# Pinout.net
KiCad netlist of a schematic drawn in Altium Designer
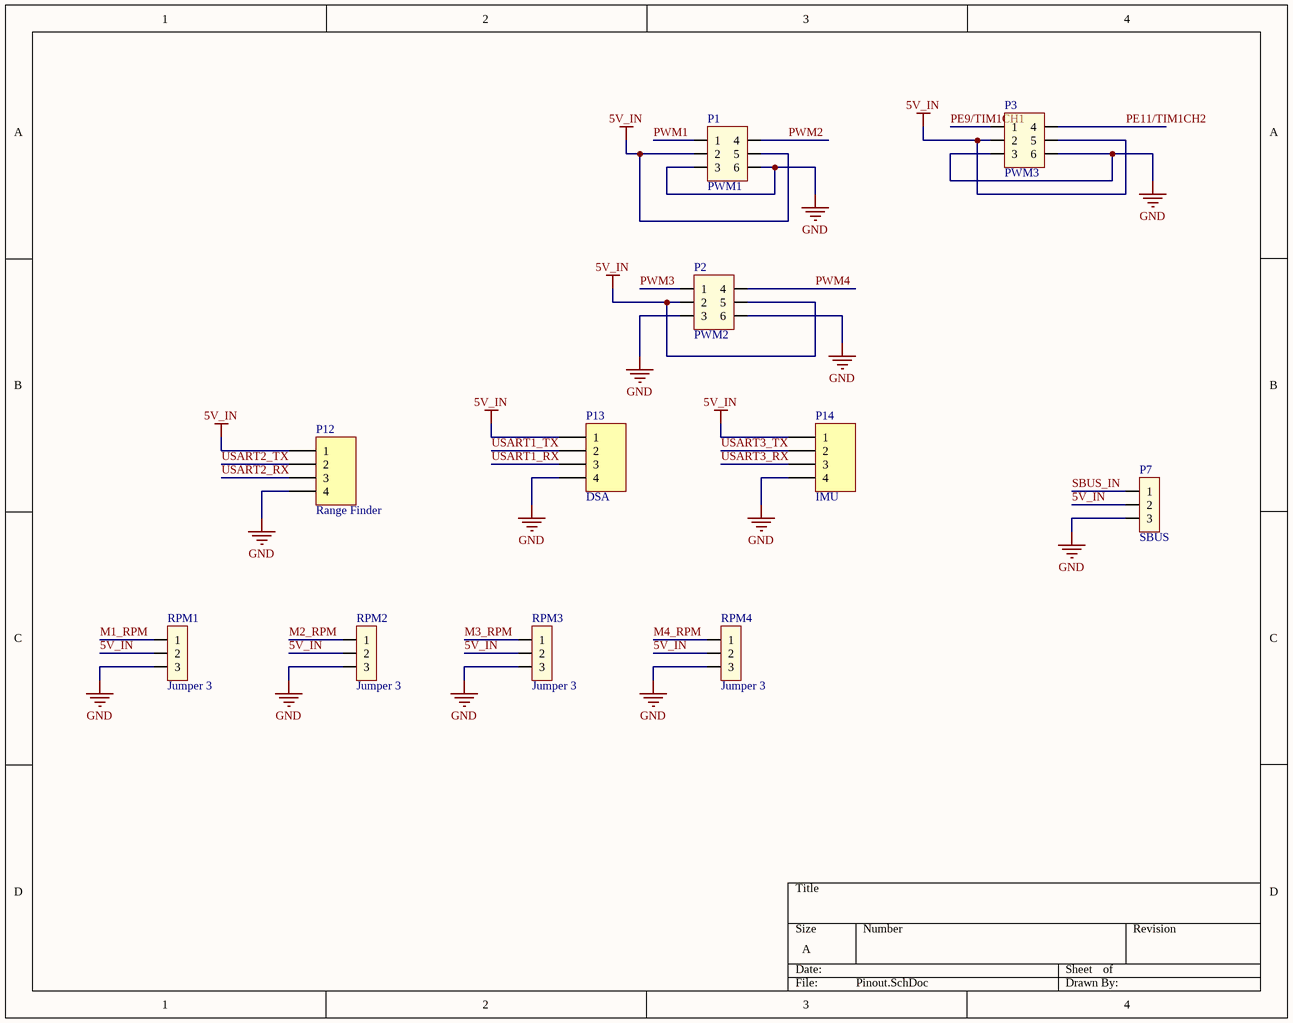
[diagram p0: Pinout.SchDoc]

(export (version "E")
  (design (tool "Eeschema 10.0.6"))
  (components
    (comp (ref "P1")
      (value "PWM1")
      (footprint "JP3x2")
      (description "Connector 3x2")
      (libsource (lib "syhaunguyen") (part "JP3x2"))
    )
    (comp (ref "P2")
      (value "PWM2")
      (footprint "JP3x2")
      (description "Connector 3x2")
      (libsource (lib "syhaunguyen") (part "JP3x2"))
    )
    (comp (ref "P3")
      (value "PWM3")
      (footprint "JP3x2")
      (description "Connector 3x2")
      (libsource (lib "syhaunguyen") (part "JP3x2"))
    )
    (comp (ref "P7")
      (value "SBUS")
      (footprint "JP3")
      (description "Jumper 3")
      (libsource (lib "syhaunguyen") (part "JP3"))
    )
    (comp (ref "P12")
      (value "Range Finder")
      (footprint "HDR1X4")
      (description "Header, 4-Pin")
      (fields (field (name "PUBLISHER") "Altium Limited"))
      (libsource (lib "Miscellaneous Connectors") (part "Header 4"))
    )
    (comp (ref "P13")
      (value "DSA")
      (footprint "HDR1X4")
      (description "Header, 4-Pin")
      (fields (field (name "PUBLISHER") "Altium Limited"))
      (libsource (lib "Miscellaneous Connectors") (part "Header 4"))
    )
    (comp (ref "P14")
      (value "IMU")
      (footprint "HDR1X4")
      (description "Header, 4-Pin")
      (fields (field (name "PUBLISHER") "Altium Limited"))
      (libsource (lib "Miscellaneous Connectors") (part "Header 4"))
    )
    (comp (ref "RPM1") (value "Jumper 3") (footprint "JP3") (libsource (lib "syhaunguyen") (part "JP3")))
    (comp (ref "RPM2") (value "Jumper 3") (footprint "JP3") (libsource (lib "syhaunguyen") (part "JP3")))
    (comp (ref "RPM3") (value "Jumper 3") (footprint "JP3") (libsource (lib "syhaunguyen") (part "JP3")))
    (comp (ref "RPM4") (value "Jumper 3") (footprint "JP3") (libsource (lib "syhaunguyen") (part "JP3")))
  )
  (nets
    (net (code "1") (name "/M1_RPM") (class "Default")
      (node (ref "RPM1") (pin "1") (pinfunction "1_1") (pintype "passive"))
    )
    (net (code "2") (name "/M2_RPM") (class "Default")
      (node (ref "RPM2") (pin "1") (pinfunction "1_1") (pintype "passive"))
    )
    (net (code "3") (name "/M3_RPM") (class "Default")
      (node (ref "RPM3") (pin "1") (pinfunction "1_1") (pintype "passive"))
    )
    (net (code "4") (name "/M4_RPM") (class "Default")
      (node (ref "RPM4") (pin "1") (pinfunction "1_1") (pintype "passive"))
    )
    (net (code "5") (name "/PE9{slash}TIM1CH1") (class "Default")
      (node (ref "P3") (pin "1") (pinfunction "1_1") (pintype "passive"))
    )
    (net (code "6") (name "/PE11{slash}TIM1CH2") (class "Default")
      (node (ref "P3") (pin "4") (pinfunction "4_4") (pintype "passive"))
    )
    (net (code "7") (name "/PWM1") (class "Default")
      (node (ref "P1") (pin "1") (pinfunction "1_1") (pintype "passive"))
    )
    (net (code "8") (name "/PWM2") (class "Default")
      (node (ref "P1") (pin "4") (pinfunction "4_4") (pintype "passive"))
    )
    (net (code "9") (name "/PWM3") (class "Default")
      (node (ref "P2") (pin "1") (pinfunction "1_1") (pintype "passive"))
    )
    (net (code "10") (name "/PWM4") (class "Default")
      (node (ref "P2") (pin "4") (pinfunction "4_4") (pintype "passive"))
    )
    (net (code "11") (name "/SBUS_IN") (class "Default")
      (node (ref "P7") (pin "1") (pinfunction "1_1") (pintype "passive"))
    )
    (net (code "12") (name "/USART1_RX") (class "Default")
      (node (ref "P13") (pin "3") (pinfunction "3_3") (pintype "passive"))
    )
    (net (code "13") (name "/USART1_TX") (class "Default")
      (node (ref "P13") (pin "2") (pinfunction "2_2") (pintype "passive"))
    )
    (net (code "14") (name "/USART2_RX") (class "Default")
      (node (ref "P12") (pin "3") (pinfunction "3_3") (pintype "passive"))
    )
    (net (code "15") (name "/USART2_TX") (class "Default")
      (node (ref "P12") (pin "2") (pinfunction "2_2") (pintype "passive"))
    )
    (net (code "16") (name "/USART3_RX") (class "Default")
      (node (ref "P14") (pin "3") (pinfunction "3_3") (pintype "passive"))
    )
    (net (code "17") (name "/USART3_TX") (class "Default")
      (node (ref "P14") (pin "2") (pinfunction "2_2") (pintype "passive"))
    )
    (net (code "18") (name "5V_IN") (class "Default")
      (node (ref "P1") (pin "2") (pinfunction "2_2") (pintype "passive"))
      (node (ref "P1") (pin "5") (pinfunction "5_5") (pintype "passive"))
      (node (ref "P12") (pin "1") (pinfunction "1_1") (pintype "passive"))
      (node (ref "P13") (pin "1") (pinfunction "1_1") (pintype "passive"))
      (node (ref "P14") (pin "1") (pinfunction "1_1") (pintype "passive"))
      (node (ref "P2") (pin "2") (pinfunction "2_2") (pintype "passive"))
      (node (ref "P2") (pin "5") (pinfunction "5_5") (pintype "passive"))
      (node (ref "P3") (pin "2") (pinfunction "2_2") (pintype "passive"))
      (node (ref "P3") (pin "5") (pinfunction "5_5") (pintype "passive"))
      (node (ref "P7") (pin "2") (pinfunction "2_2") (pintype "passive"))
      (node (ref "RPM1") (pin "2") (pinfunction "2_2") (pintype "passive"))
      (node (ref "RPM2") (pin "2") (pinfunction "2_2") (pintype "passive"))
      (node (ref "RPM3") (pin "2") (pinfunction "2_2") (pintype "passive"))
      (node (ref "RPM4") (pin "2") (pinfunction "2_2") (pintype "passive"))
    )
    (net (code "19") (name "GND") (class "Default")
      (node (ref "P1") (pin "3") (pinfunction "3_3") (pintype "passive"))
      (node (ref "P1") (pin "6") (pinfunction "6_6") (pintype "passive"))
      (node (ref "P12") (pin "4") (pinfunction "4_4") (pintype "passive"))
      (node (ref "P13") (pin "4") (pinfunction "4_4") (pintype "passive"))
      (node (ref "P14") (pin "4") (pinfunction "4_4") (pintype "passive"))
      (node (ref "P2") (pin "3") (pinfunction "3_3") (pintype "passive"))
      (node (ref "P2") (pin "6") (pinfunction "6_6") (pintype "passive"))
      (node (ref "P3") (pin "3") (pinfunction "3_3") (pintype "passive"))
      (node (ref "P3") (pin "6") (pinfunction "6_6") (pintype "passive"))
      (node (ref "P7") (pin "3") (pinfunction "3_3") (pintype "passive"))
      (node (ref "RPM1") (pin "3") (pinfunction "3_3") (pintype "passive"))
      (node (ref "RPM2") (pin "3") (pinfunction "3_3") (pintype "passive"))
      (node (ref "RPM3") (pin "3") (pinfunction "3_3") (pintype "passive"))
      (node (ref "RPM4") (pin "3") (pinfunction "3_3") (pintype "passive"))
    )
  )
)
